# Geass_Chaser_Nov_11_2025.net
KiCad netlist of a schematic drawn in EasyEDA
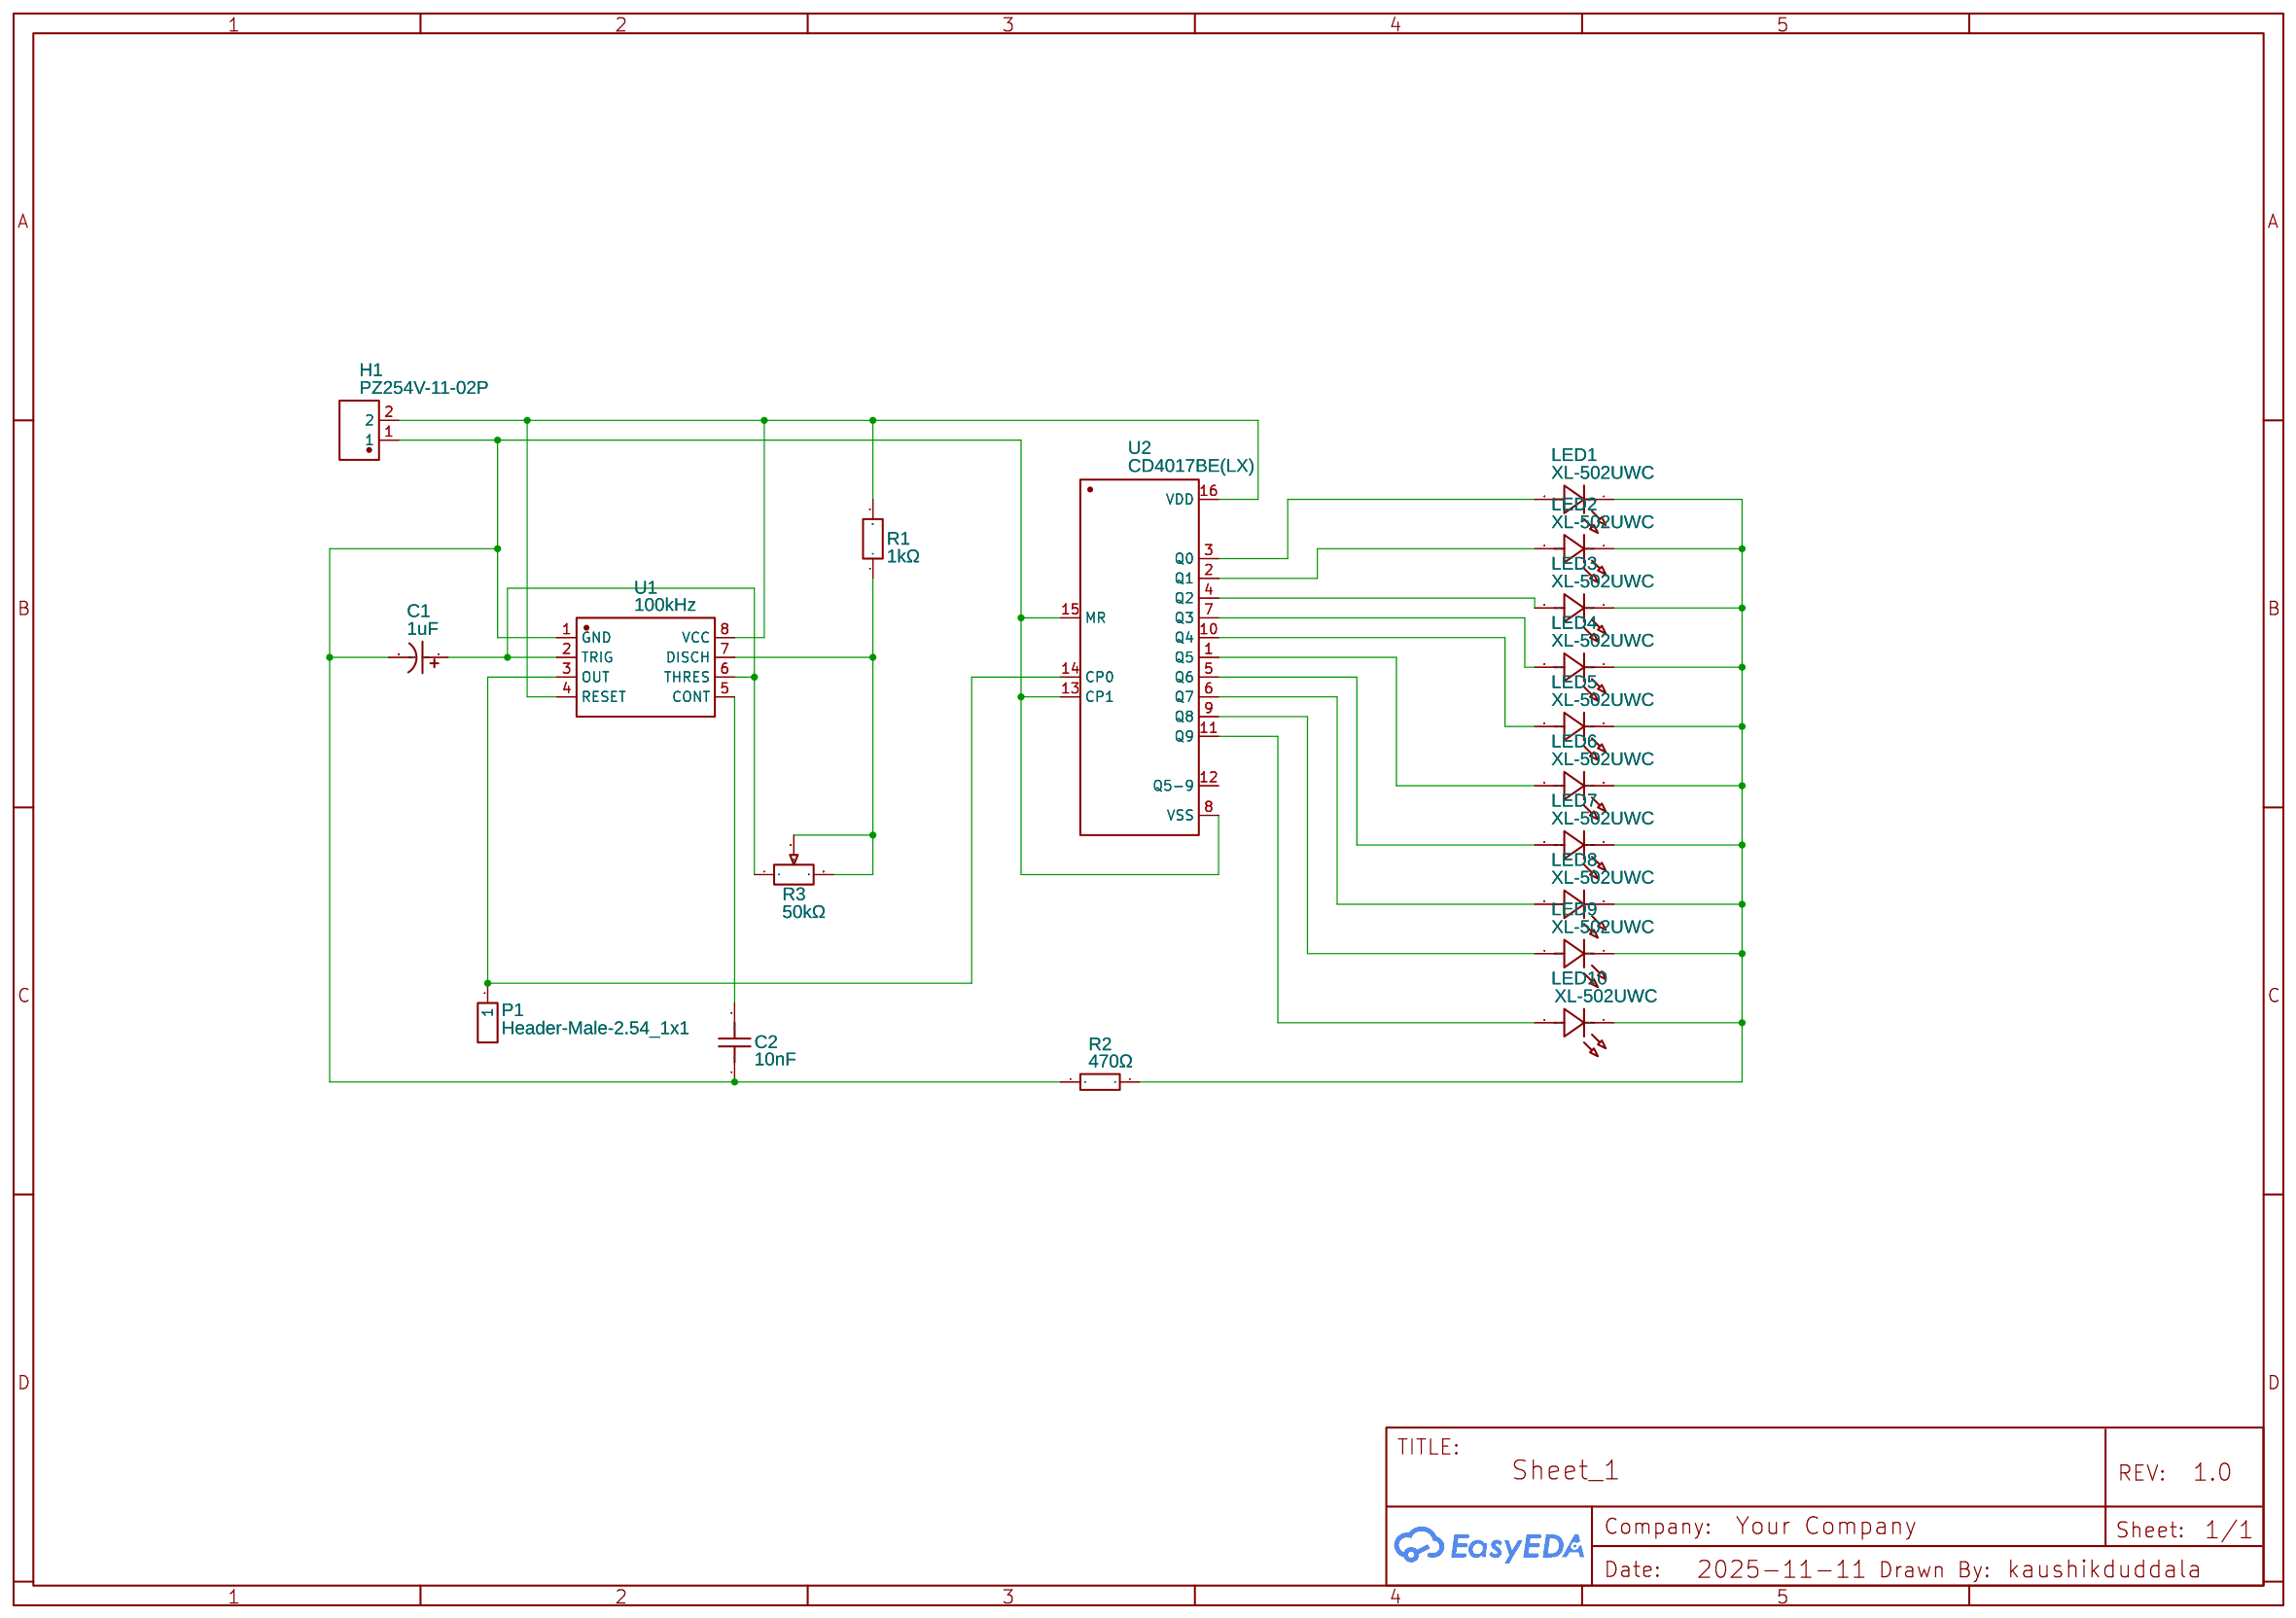
[diagram p0: schematic sheet]

(export (version "E")
  (design (tool "Eeschema 10.0.6"))
  (components
    (comp (ref "C1")
      (value "1uF")
      (fields (field (name "Manufacturer Part") "KF010M050C110A") (field (name "Manufacturer") "CapXon(丰宾)"))
      (libsource (lib "") (part "KF010M050C110A"))
    )
    (comp (ref "C2")
      (value "10nF")
      (fields (field (name "Manufacturer Part") "N09F1B103MN0B0S0N0") (field (name "Manufacturer") "STE(松田)"))
      (libsource (lib "") (part "N09F1B103MN0B0S0N0"))
    )
    (comp (ref "H1")
      (value "PZ254V-11-02P")
      (fields (field (name "Manufacturer") "XFCN(兴飞)"))
      (libsource (lib "") (part "PZ254V-11-02P"))
    )
    (comp (ref "LED1")
      (value "XL-502UWC")
      (fields (field (name "Manufacturer") "XINGLIGHT(成兴光)"))
      (libsource (lib "") (part "XL-502UWC"))
    )
    (comp (ref "LED2")
      (value "XL-502UWC")
      (fields (field (name "Manufacturer") "XINGLIGHT(成兴光)"))
      (libsource (lib "") (part "XL-502UWC"))
    )
    (comp (ref "LED3")
      (value "XL-502UWC")
      (fields (field (name "Manufacturer") "XINGLIGHT(成兴光)"))
      (libsource (lib "") (part "XL-502UWC"))
    )
    (comp (ref "LED4")
      (value "XL-502UWC")
      (fields (field (name "Manufacturer") "XINGLIGHT(成兴光)"))
      (libsource (lib "") (part "XL-502UWC"))
    )
    (comp (ref "LED5")
      (value "XL-502UWC")
      (fields (field (name "Manufacturer") "XINGLIGHT(成兴光)"))
      (libsource (lib "") (part "XL-502UWC"))
    )
    (comp (ref "LED6")
      (value "XL-502UWC")
      (fields (field (name "Manufacturer") "XINGLIGHT(成兴光)"))
      (libsource (lib "") (part "XL-502UWC"))
    )
    (comp (ref "LED7")
      (value "XL-502UWC")
      (fields (field (name "Manufacturer") "XINGLIGHT(成兴光)"))
      (libsource (lib "") (part "XL-502UWC"))
    )
    (comp (ref "LED8")
      (value "XL-502UWC")
      (fields (field (name "Manufacturer") "XINGLIGHT(成兴光)"))
      (libsource (lib "") (part "XL-502UWC"))
    )
    (comp (ref "LED9")
      (value "XL-502UWC")
      (fields (field (name "Manufacturer") "XINGLIGHT(成兴光)"))
      (libsource (lib "") (part "XL-502UWC"))
    )
    (comp (ref "LED10")
      (value "XL-502UWC")
      (fields (field (name "Manufacturer") "XINGLIGHT(成兴光)"))
      (libsource (lib "") (part "XL-502UWC"))
    )
    (comp (ref "P1")
      (value "Header-Male-2.54_1x1")
      (fields (field (name "Manufacturer Part") "2.54-1*1P针") (field (name "Manufacturer") "BOOMELE(博穆精密)"))
      (libsource (lib "") (part "Header-Male-2.54_1x1"))
    )
    (comp (ref "R1")
      (value "1kΩ")
      (fields (field (name "Manufacturer Part") "MF1/4W-1KΩ±1%T52") (field (name "Manufacturer") "华星机电"))
      (libsource (lib "") (part "MF1/4W-1KΩ±1%T52"))
    )
    (comp (ref "R2")
      (value "470Ω")
      (fields
        (field (name "Manufacturer Part") "MFR0W4F4700A50")
        (field (name "Manufacturer") "UNI-ROYAL(厚声)")
      )
      (libsource (lib "") (part "MFR0W4F4700A50"))
    )
    (comp (ref "R3")
      (value "50kΩ")
      (fields (field (name "Manufacturer Part") "3296X-1-503") (field (name "Manufacturer") "BOCHEN(博晨)"))
      (libsource (lib "") (part "3296X-1-503_C118912"))
    )
    (comp (ref "U1")
      (value "100kHz")
      (fields (field (name "Manufacturer Part") "NE555P") (field (name "Manufacturer") "TI(德州仪器)"))
      (libsource (lib "") (part "NE555P"))
    )
    (comp (ref "U2")
      (value "CD4017BE(LX)")
      (fields (field (name "Manufacturer") "LX(灵星芯微)"))
      (libsource (lib "") (part "CD4017BE(LX)"))
    )
  )
  (nets
    (net (code "1") (name "Net-(LED1-A)") (class "Default")
      (node (ref "LED1") (pin "2") (pinfunction "A_2") (pintype "unspecified"))
      (node (ref "U2") (pin "3") (pinfunction "Q0_3") (pintype "unspecified"))
    )
    (net (code "2") (name "Net-(LED1-K)") (class "Default")
      (node (ref "LED1") (pin "1") (pinfunction "K_1") (pintype "unspecified"))
      (node (ref "LED10") (pin "1") (pinfunction "K_1") (pintype "unspecified"))
      (node (ref "LED2") (pin "1") (pinfunction "K_1") (pintype "unspecified"))
      (node (ref "LED3") (pin "1") (pinfunction "K_1") (pintype "unspecified"))
      (node (ref "LED4") (pin "1") (pinfunction "K_1") (pintype "unspecified"))
      (node (ref "LED5") (pin "1") (pinfunction "K_1") (pintype "unspecified"))
      (node (ref "LED6") (pin "1") (pinfunction "K_1") (pintype "unspecified"))
      (node (ref "LED7") (pin "1") (pinfunction "K_1") (pintype "unspecified"))
      (node (ref "LED8") (pin "1") (pinfunction "K_1") (pintype "unspecified"))
      (node (ref "LED9") (pin "1") (pinfunction "K_1") (pintype "unspecified"))
      (node (ref "R2") (pin "2") (pinfunction "2_2") (pintype "input"))
    )
    (net (code "3") (name "Net-(LED2-A)") (class "Default")
      (node (ref "LED2") (pin "2") (pinfunction "A_2") (pintype "unspecified"))
      (node (ref "U2") (pin "2") (pinfunction "Q1_2") (pintype "unspecified"))
    )
    (net (code "4") (name "Net-(LED3-A)") (class "Default")
      (node (ref "LED3") (pin "2") (pinfunction "A_2") (pintype "unspecified"))
      (node (ref "U2") (pin "4") (pinfunction "Q2_4") (pintype "unspecified"))
    )
    (net (code "5") (name "Net-(LED4-A)") (class "Default")
      (node (ref "LED4") (pin "2") (pinfunction "A_2") (pintype "unspecified"))
      (node (ref "U2") (pin "7") (pinfunction "Q3_7") (pintype "unspecified"))
    )
    (net (code "6") (name "Net-(LED5-A)") (class "Default")
      (node (ref "LED5") (pin "2") (pinfunction "A_2") (pintype "unspecified"))
      (node (ref "U2") (pin "10") (pinfunction "Q4_10") (pintype "unspecified"))
    )
    (net (code "7") (name "Net-(LED6-A)") (class "Default")
      (node (ref "LED6") (pin "2") (pinfunction "A_2") (pintype "unspecified"))
      (node (ref "U2") (pin "1") (pinfunction "Q5_1") (pintype "unspecified"))
    )
    (net (code "8") (name "Net-(LED7-A)") (class "Default")
      (node (ref "LED7") (pin "2") (pinfunction "A_2") (pintype "unspecified"))
      (node (ref "U2") (pin "5") (pinfunction "Q6_5") (pintype "unspecified"))
    )
    (net (code "9") (name "Net-(LED8-A)") (class "Default")
      (node (ref "LED8") (pin "2") (pinfunction "A_2") (pintype "unspecified"))
      (node (ref "U2") (pin "6") (pinfunction "Q7_6") (pintype "unspecified"))
    )
    (net (code "10") (name "Net-(LED9-A)") (class "Default")
      (node (ref "LED9") (pin "2") (pinfunction "A_2") (pintype "unspecified"))
      (node (ref "U2") (pin "9") (pinfunction "Q8_9") (pintype "unspecified"))
    )
    (net (code "11") (name "Net-(LED10-A)") (class "Default")
      (node (ref "LED10") (pin "2") (pinfunction "A_2") (pintype "unspecified"))
      (node (ref "U2") (pin "11") (pinfunction "Q9_11") (pintype "unspecified"))
    )
    (net (code "12") (name "Net-(U1-CONT)") (class "Default")
      (node (ref "C2") (pin "2") (pinfunction "2_2") (pintype "unspecified"))
      (node (ref "U1") (pin "5") (pinfunction "CONT_5") (pintype "unspecified"))
    )
    (net (code "13") (name "Net-(U1-DISCH)") (class "Default")
      (node (ref "R1") (pin "1") (pinfunction "1_1") (pintype "unspecified"))
      (node (ref "R3") (pin "2") (pinfunction "2_2") (pintype "input"))
      (node (ref "R3") (pin "3") (pinfunction "3_3") (pintype "input"))
      (node (ref "U1") (pin "7") (pinfunction "DISCH_7") (pintype "unspecified"))
    )
    (net (code "14") (name "Net-(U1-GND)") (class "Default")
      (node (ref "C1") (pin "2") (pinfunction "2_2") (pintype "input"))
      (node (ref "C2") (pin "1") (pinfunction "1_1") (pintype "unspecified"))
      (node (ref "H1") (pin "1") (pinfunction "1_1") (pintype "unspecified"))
      (node (ref "R2") (pin "1") (pinfunction "1_1") (pintype "input"))
      (node (ref "U1") (pin "1") (pinfunction "GND_1") (pintype "unspecified"))
      (node (ref "U2") (pin "13") (pinfunction "CP1_13") (pintype "unspecified"))
      (node (ref "U2") (pin "15") (pinfunction "MR_15") (pintype "unspecified"))
      (node (ref "U2") (pin "8") (pinfunction "VSS_8") (pintype "unspecified"))
    )
    (net (code "15") (name "Net-(U1-OUT)") (class "Default")
      (node (ref "P1") (pin "1") (pinfunction "1_1") (pintype "input"))
      (node (ref "U1") (pin "3") (pinfunction "OUT_3") (pintype "unspecified"))
      (node (ref "U2") (pin "14") (pinfunction "CP0_14") (pintype "unspecified"))
    )
    (net (code "16") (name "Net-(U1-RESET)") (class "Default")
      (node (ref "H1") (pin "2") (pinfunction "2_2") (pintype "unspecified"))
      (node (ref "R1") (pin "2") (pinfunction "2_2") (pintype "unspecified"))
      (node (ref "U1") (pin "4") (pinfunction "RESET_4") (pintype "unspecified"))
      (node (ref "U1") (pin "8") (pinfunction "VCC_8") (pintype "unspecified"))
      (node (ref "U2") (pin "16") (pinfunction "VDD_16") (pintype "unspecified"))
    )
    (net (code "17") (name "Net-(U1-THRES)") (class "Default")
      (node (ref "C1") (pin "1") (pinfunction "1_1") (pintype "input"))
      (node (ref "R3") (pin "1") (pinfunction "1_1") (pintype "input"))
      (node (ref "U1") (pin "2") (pinfunction "TRIG_2") (pintype "unspecified"))
      (node (ref "U1") (pin "6") (pinfunction "THRES_6") (pintype "unspecified"))
    )
    (net (code "18") (name "unconnected-(U2-Q5-9-Pad12)") (class "Default")
      (node (ref "U2") (pin "12") (pinfunction "Q5-9_12") (pintype "unspecified"))
    )
  )
)
